# PowerDistributionBoard.net
KiCad netlist of a schematic drawn in EAGLE
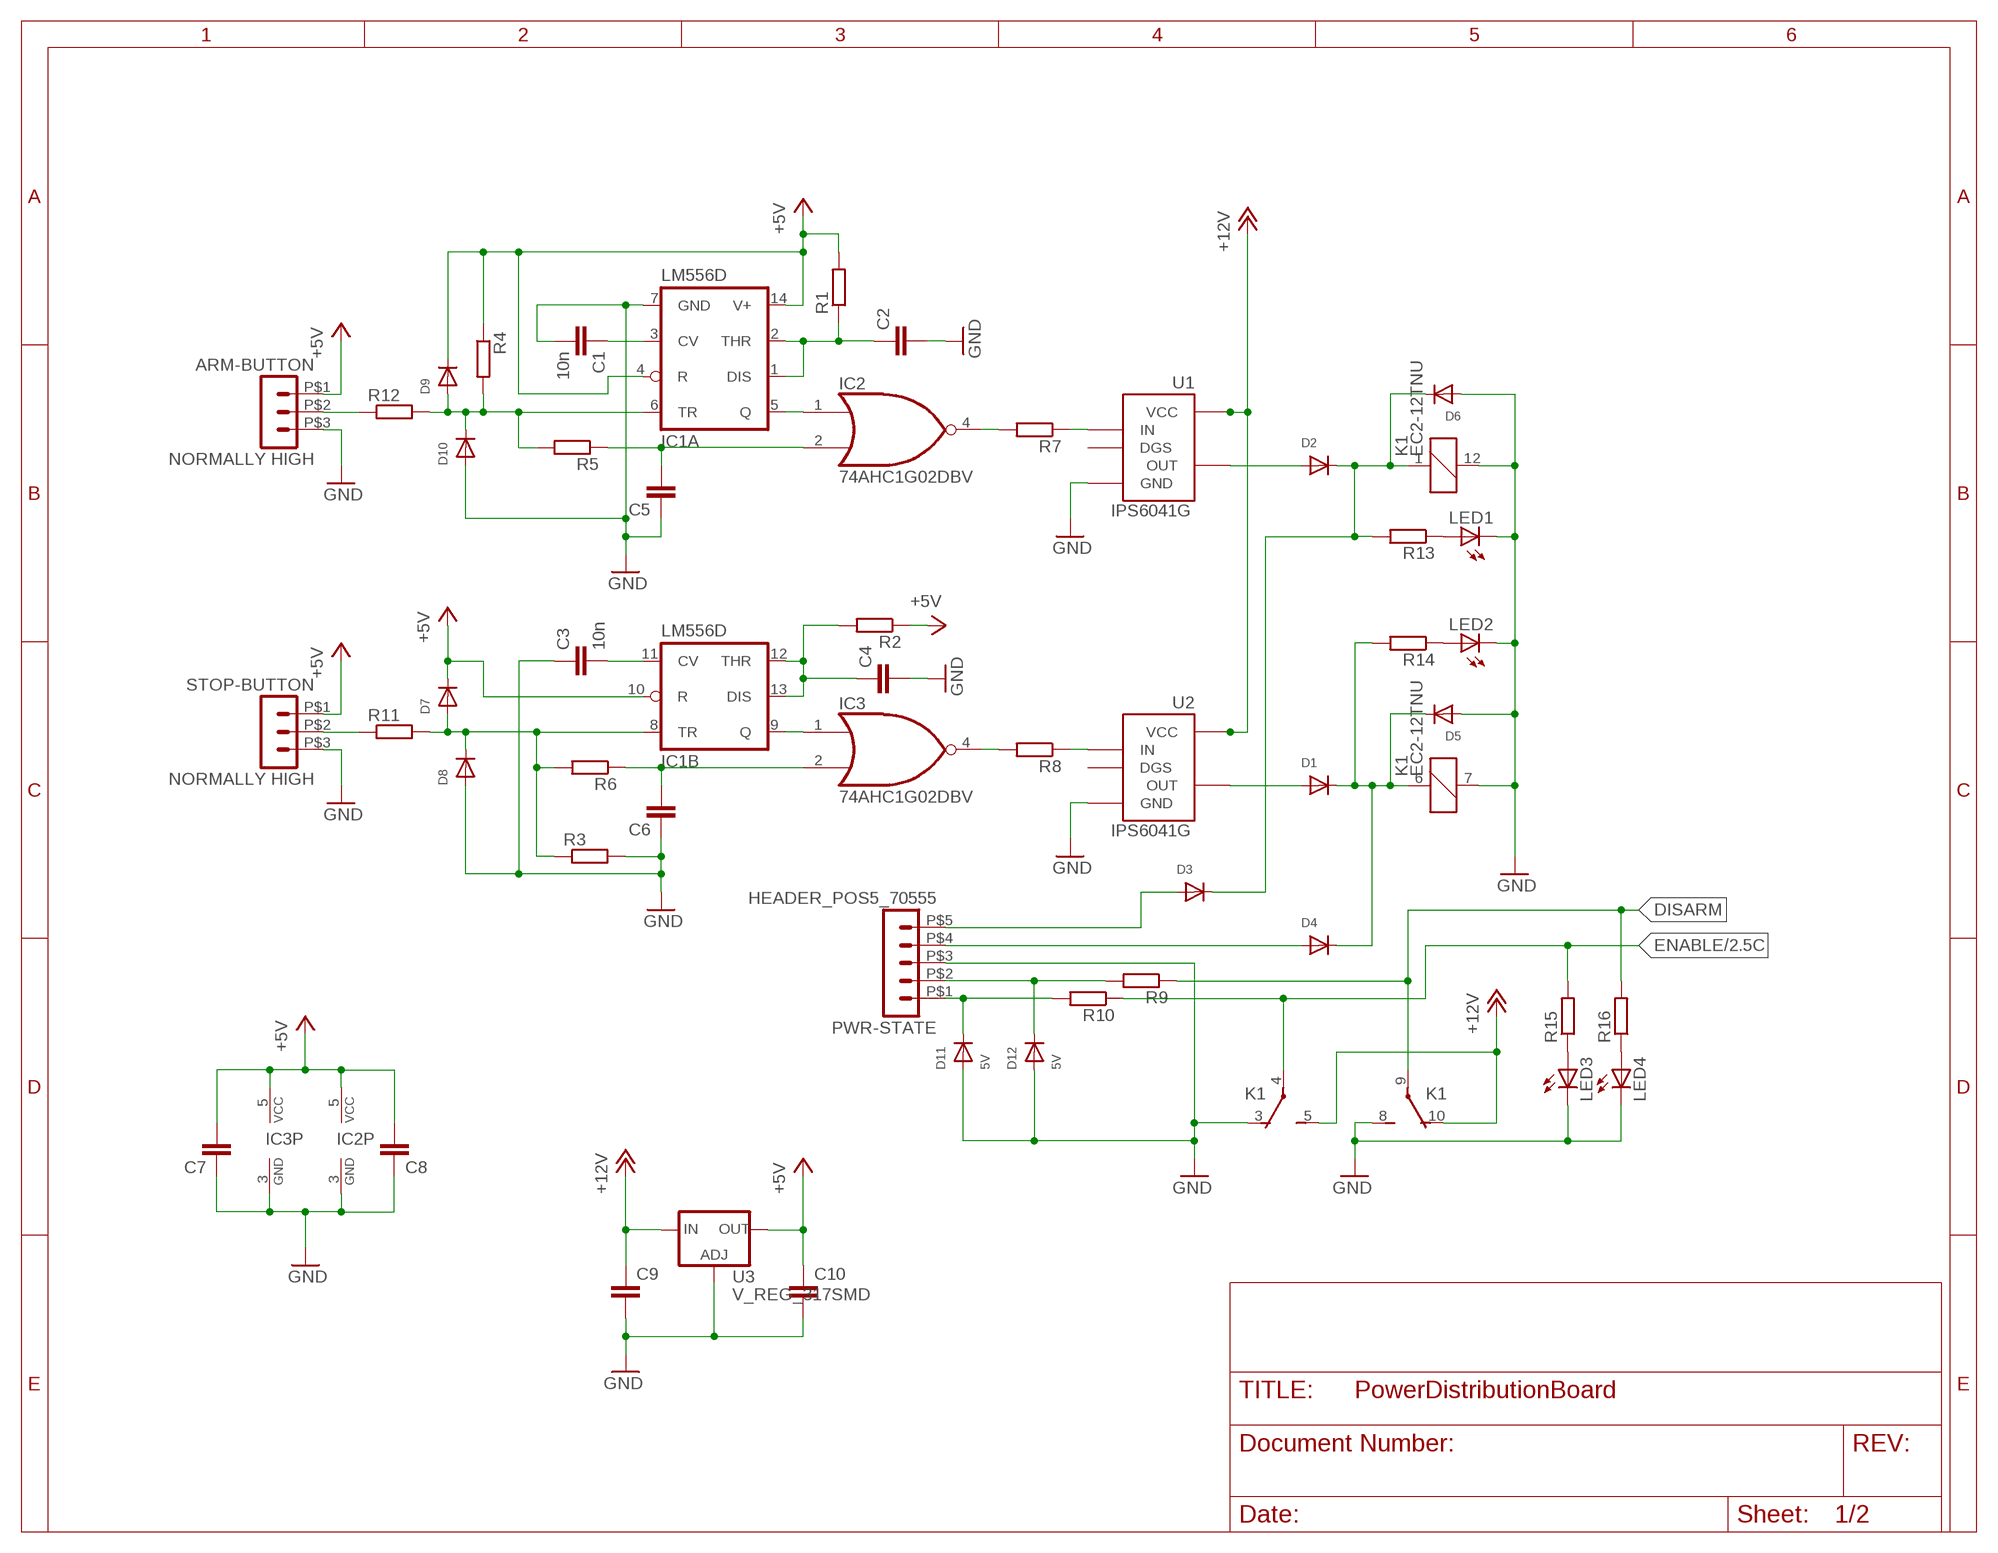
[diagram p0: schematic, sheet 1]
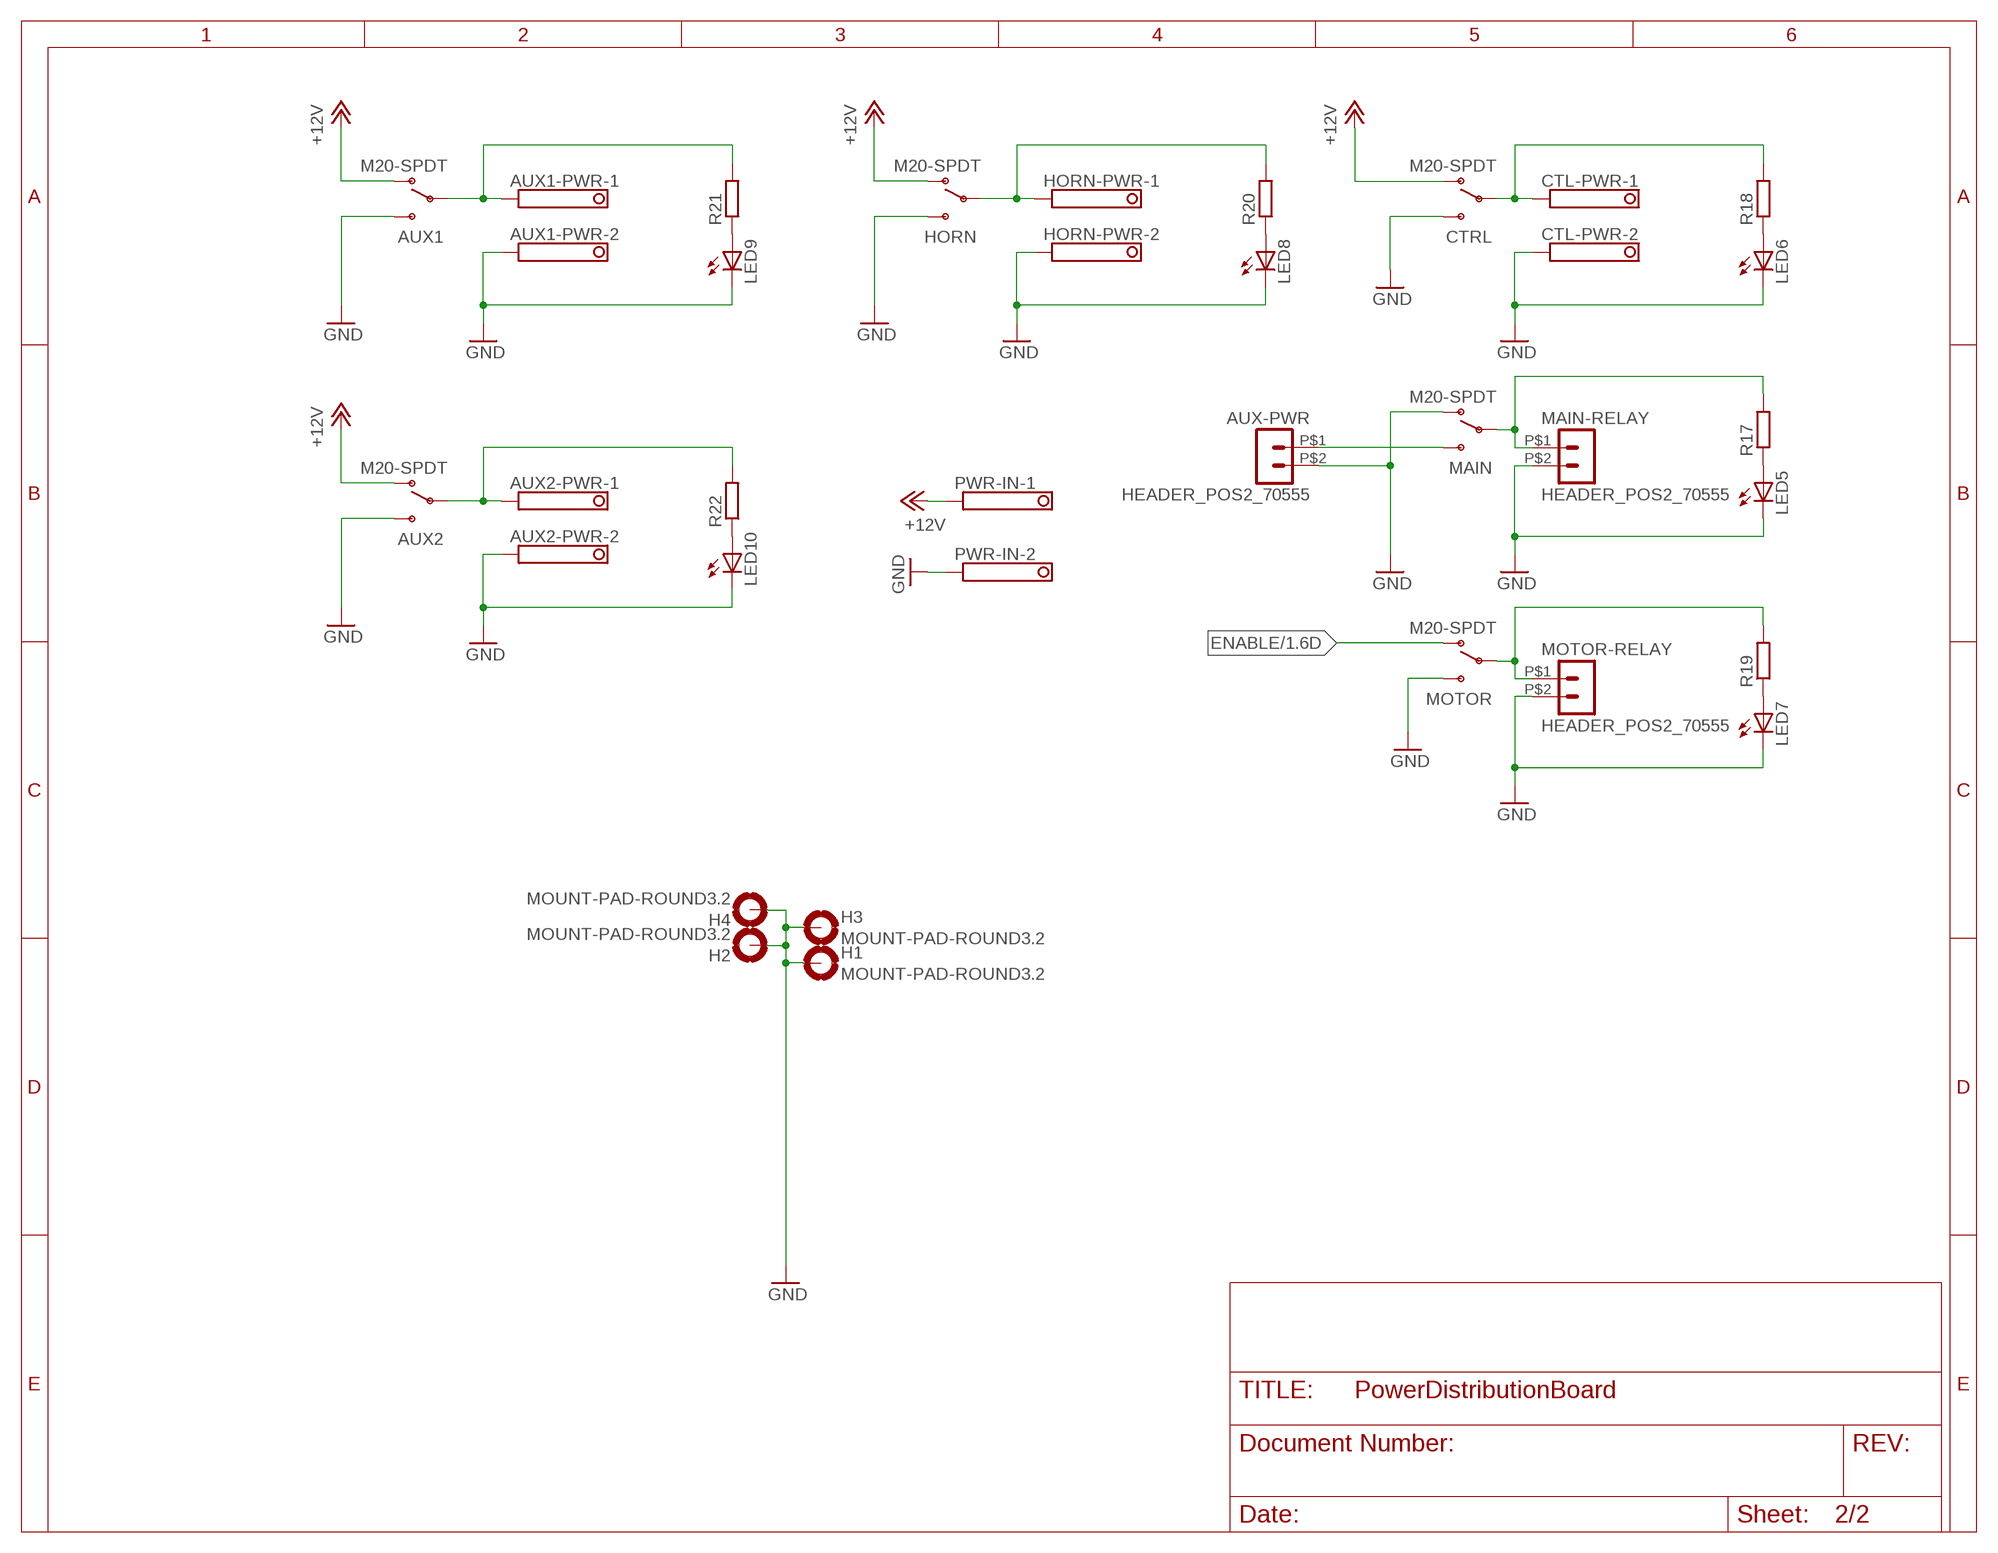
[diagram p1: schematic, sheet 2]

(export (version "E")
  (design (tool "Eeschema 10.0.6"))
  (components
    (comp (ref "ARM-BUTTON")
      (value "NORMALLY HIGH")
      (footprint "eagle-import:70555-POS3")
      (libsource (lib "eagle-import") (part "HEADER_POS3_?70555"))
    )
    (comp (ref "C1")
      (value "10n")
      (footprint "eagle-import:C0603")
      (libsource (lib "eagle-import") (part "C-EUC0603"))
    )
    (comp (ref "C2")
      (value "C-EUC0603")
      (footprint "eagle-import:C0603")
      (libsource (lib "eagle-import") (part "C-EUC0603"))
    )
    (comp (ref "C3")
      (value "10n")
      (footprint "eagle-import:C0603")
      (libsource (lib "eagle-import") (part "C-EUC0603"))
    )
    (comp (ref "C4")
      (value "C-EUC0603")
      (footprint "eagle-import:C0603")
      (libsource (lib "eagle-import") (part "C-EUC0603"))
    )
    (comp (ref "C5")
      (value "C-EUC0603")
      (footprint "eagle-import:C0603")
      (libsource (lib "eagle-import") (part "C-EUC0603"))
    )
    (comp (ref "C6")
      (value "C-EUC0603")
      (footprint "eagle-import:C0603")
      (libsource (lib "eagle-import") (part "C-EUC0603"))
    )
    (comp (ref "C7")
      (value "C-EUC0603")
      (footprint "eagle-import:C0603")
      (libsource (lib "eagle-import") (part "C-EUC0603"))
    )
    (comp (ref "C8")
      (value "C-EUC0603")
      (footprint "eagle-import:C0603")
      (libsource (lib "eagle-import") (part "C-EUC0603"))
    )
    (comp (ref "C9")
      (value "C-EUC1206")
      (footprint "eagle-import:C1206")
      (libsource (lib "eagle-import") (part "C-EUC1206"))
    )
    (comp (ref "C10")
      (value "C-EUC1206")
      (footprint "eagle-import:C1206")
      (libsource (lib "eagle-import") (part "C-EUC1206"))
    )
    (comp (ref "D1")
      (value "DIODESOD-123")
      (footprint "eagle-import:SOD-123")
      (libsource (lib "eagle-import") (part "DIODESOD-123"))
    )
    (comp (ref "D2")
      (value "DIODESOD-123")
      (footprint "eagle-import:SOD-123")
      (libsource (lib "eagle-import") (part "DIODESOD-123"))
    )
    (comp (ref "D3")
      (value "DIODESOD-123")
      (footprint "eagle-import:SOD-123")
      (libsource (lib "eagle-import") (part "DIODESOD-123"))
    )
    (comp (ref "D4")
      (value "DIODESOD-123")
      (footprint "eagle-import:SOD-123")
      (libsource (lib "eagle-import") (part "DIODESOD-123"))
    )
    (comp (ref "D5")
      (value "DIODESOD-123")
      (footprint "eagle-import:SOD-123")
      (libsource (lib "eagle-import") (part "DIODESOD-123"))
    )
    (comp (ref "D6")
      (value "DIODESOD-123")
      (footprint "eagle-import:SOD-123")
      (libsource (lib "eagle-import") (part "DIODESOD-123"))
    )
    (comp (ref "D7")
      (value "DIODESOD-123")
      (footprint "eagle-import:SOD-123")
      (libsource (lib "eagle-import") (part "DIODESOD-123"))
    )
    (comp (ref "D8")
      (value "DIODESOD-123")
      (footprint "eagle-import:SOD-123")
      (libsource (lib "eagle-import") (part "DIODESOD-123"))
    )
    (comp (ref "D9")
      (value "DIODESOD-123")
      (footprint "eagle-import:SOD-123")
      (libsource (lib "eagle-import") (part "DIODESOD-123"))
    )
    (comp (ref "D10")
      (value "DIODESOD-123")
      (footprint "eagle-import:SOD-123")
      (libsource (lib "eagle-import") (part "DIODESOD-123"))
    )
    (comp (ref "D11")
      (value "5V")
      (footprint "eagle-import:SOD-123")
      (libsource (lib "eagle-import") (part "DIODESOD-123"))
    )
    (comp (ref "D12")
      (value "5V")
      (footprint "eagle-import:SOD-123")
      (libsource (lib "eagle-import") (part "DIODESOD-123"))
    )
    (comp (ref "IC1")
      (value "LM556D")
      (footprint "eagle-import:SO14")
      (libsource (lib "eagle-import") (part "556DLM"))
    )
    (comp (ref "IC2")
      (value "74AHC1G02DBV")
      (footprint "eagle-import:SOT23-5")
      (libsource (lib "eagle-import") (part "741G02DBVAHC"))
    )
    (comp (ref "IC3")
      (value "74AHC1G02DBV")
      (footprint "eagle-import:SOT23-5")
      (libsource (lib "eagle-import") (part "741G02DBVAHC"))
    )
    (comp (ref "K1")
      (value "EC2-12TNU")
      (footprint "eagle-import:EC2-_TNU")
      (fields (field (name "PARTNO") "EC2-12TNU"))
      (libsource (lib "eagle-import") (part "EC2-12TNU"))
    )
    (comp (ref "LED1")
      (value "LEDCHIP-LED0805")
      (footprint "eagle-import:CHIP-LED0805")
      (libsource (lib "eagle-import") (part "LEDCHIP-LED0805"))
    )
    (comp (ref "LED2")
      (value "LEDCHIP-LED0805")
      (footprint "eagle-import:CHIP-LED0805")
      (libsource (lib "eagle-import") (part "LEDCHIP-LED0805"))
    )
    (comp (ref "LED3")
      (value "LEDCHIP-LED0805")
      (footprint "eagle-import:CHIP-LED0805")
      (libsource (lib "eagle-import") (part "LEDCHIP-LED0805"))
    )
    (comp (ref "LED4")
      (value "LEDCHIP-LED0805")
      (footprint "eagle-import:CHIP-LED0805")
      (libsource (lib "eagle-import") (part "LEDCHIP-LED0805"))
    )
    (comp (ref "PWR-STATE")
      (value "HEADER_POS5_70555")
      (footprint "eagle-import:70555-POS5")
      (libsource (lib "eagle-import") (part "HEADER_POS5_?70555"))
    )
    (comp (ref "R1")
      (value "R-EU_R0603")
      (footprint "eagle-import:R0603")
      (libsource (lib "eagle-import") (part "R-EU_R0603"))
    )
    (comp (ref "R2")
      (value "R-EU_R0603")
      (footprint "eagle-import:R0603")
      (libsource (lib "eagle-import") (part "R-EU_R0603"))
    )
    (comp (ref "R3")
      (value "R-EU_R0603")
      (footprint "eagle-import:R0603")
      (libsource (lib "eagle-import") (part "R-EU_R0603"))
    )
    (comp (ref "R4")
      (value "R-EU_R0603")
      (footprint "eagle-import:R0603")
      (libsource (lib "eagle-import") (part "R-EU_R0603"))
    )
    (comp (ref "R5")
      (value "R-EU_R0603")
      (footprint "eagle-import:R0603")
      (libsource (lib "eagle-import") (part "R-EU_R0603"))
    )
    (comp (ref "R6")
      (value "R-EU_R0603")
      (footprint "eagle-import:R0603")
      (libsource (lib "eagle-import") (part "R-EU_R0603"))
    )
    (comp (ref "R7")
      (value "R-EU_R0603")
      (footprint "eagle-import:R0603")
      (libsource (lib "eagle-import") (part "R-EU_R0603"))
    )
    (comp (ref "R8")
      (value "R-EU_R0603")
      (footprint "eagle-import:R0603")
      (libsource (lib "eagle-import") (part "R-EU_R0603"))
    )
    (comp (ref "R9")
      (value "R-EU_R0603")
      (footprint "eagle-import:R0603")
      (libsource (lib "eagle-import") (part "R-EU_R0603"))
    )
    (comp (ref "R10")
      (value "R-EU_R0603")
      (footprint "eagle-import:R0603")
      (libsource (lib "eagle-import") (part "R-EU_R0603"))
    )
    (comp (ref "R11")
      (value "R-EU_R0603")
      (footprint "eagle-import:R0603")
      (libsource (lib "eagle-import") (part "R-EU_R0603"))
    )
    (comp (ref "R12")
      (value "R-EU_R0603")
      (footprint "eagle-import:R0603")
      (libsource (lib "eagle-import") (part "R-EU_R0603"))
    )
    (comp (ref "R13")
      (value "R-EU_R0603")
      (footprint "eagle-import:R0603")
      (libsource (lib "eagle-import") (part "R-EU_R0603"))
    )
    (comp (ref "R14")
      (value "R-EU_R0603")
      (footprint "eagle-import:R0603")
      (libsource (lib "eagle-import") (part "R-EU_R0603"))
    )
    (comp (ref "R15")
      (value "R-EU_R0603")
      (footprint "eagle-import:R0603")
      (libsource (lib "eagle-import") (part "R-EU_R0603"))
    )
    (comp (ref "R16")
      (value "R-EU_R0603")
      (footprint "eagle-import:R0603")
      (libsource (lib "eagle-import") (part "R-EU_R0603"))
    )
    (comp (ref "STOP-BUTTON")
      (value "NORMALLY HIGH")
      (footprint "eagle-import:70555-POS3")
      (libsource (lib "eagle-import") (part "HEADER_POS3_?70555"))
    )
    (comp (ref "U1")
      (value "IPS6041G")
      (footprint "eagle-import:SO08")
      (libsource (lib "eagle-import") (part "IPS6041G"))
    )
    (comp (ref "U2")
      (value "IPS6041G")
      (footprint "eagle-import:SO08")
      (libsource (lib "eagle-import") (part "IPS6041G"))
    )
    (comp (ref "U3")
      (value "V_REG_317SMD")
      (footprint "eagle-import:SOT223")
      (libsource (lib "eagle-import") (part "V_REG_317SMD"))
    )
    (comp (ref "AUX-PWR")
      (value "HEADER_POS2_70555")
      (footprint "eagle-import:70555-POS2")
      (libsource (lib "eagle-import") (part "HEADER_POS2_?70555"))
    )
    (comp (ref "AUX1")
      (value "M20-SPDT")
      (footprint "eagle-import:M20-SPDT")
      (libsource (lib "eagle-import") (part "M20-SPDT"))
    )
    (comp (ref "AUX1-PWR")
      (value "1751248")
      (footprint "eagle-import:1751248")
      (libsource (lib "eagle-import") (part "1751248"))
    )
    (comp (ref "AUX2")
      (value "M20-SPDT")
      (footprint "eagle-import:M20-SPDT")
      (libsource (lib "eagle-import") (part "M20-SPDT"))
    )
    (comp (ref "AUX2-PWR")
      (value "1751248")
      (footprint "eagle-import:1751248")
      (libsource (lib "eagle-import") (part "1751248"))
    )
    (comp (ref "CTL-PWR")
      (value "1751248")
      (footprint "eagle-import:1751248")
      (libsource (lib "eagle-import") (part "1751248"))
    )
    (comp (ref "CTRL")
      (value "M20-SPDT")
      (footprint "eagle-import:M20-SPDT")
      (libsource (lib "eagle-import") (part "M20-SPDT"))
    )
    (comp (ref "H1")
      (value "MOUNT-PAD-ROUND3.2")
      (footprint "eagle-import:3,2-PAD")
      (libsource (lib "eagle-import") (part "MOUNT-PAD-ROUND3.2"))
    )
    (comp (ref "H2")
      (value "MOUNT-PAD-ROUND3.2")
      (footprint "eagle-import:3,2-PAD")
      (libsource (lib "eagle-import") (part "MOUNT-PAD-ROUND3.2"))
    )
    (comp (ref "H3")
      (value "MOUNT-PAD-ROUND3.2")
      (footprint "eagle-import:3,2-PAD")
      (libsource (lib "eagle-import") (part "MOUNT-PAD-ROUND3.2"))
    )
    (comp (ref "H4")
      (value "MOUNT-PAD-ROUND3.2")
      (footprint "eagle-import:3,2-PAD")
      (libsource (lib "eagle-import") (part "MOUNT-PAD-ROUND3.2"))
    )
    (comp (ref "HORN")
      (value "M20-SPDT")
      (footprint "eagle-import:M20-SPDT")
      (libsource (lib "eagle-import") (part "M20-SPDT"))
    )
    (comp (ref "HORN-PWR")
      (value "1751248")
      (footprint "eagle-import:1751248")
      (libsource (lib "eagle-import") (part "1751248"))
    )
    (comp (ref "LED5")
      (value "LEDCHIP-LED0805")
      (footprint "eagle-import:CHIP-LED0805")
      (libsource (lib "eagle-import") (part "LEDCHIP-LED0805"))
    )
    (comp (ref "LED6")
      (value "LEDCHIP-LED0805")
      (footprint "eagle-import:CHIP-LED0805")
      (libsource (lib "eagle-import") (part "LEDCHIP-LED0805"))
    )
    (comp (ref "LED7")
      (value "LEDCHIP-LED0805")
      (footprint "eagle-import:CHIP-LED0805")
      (libsource (lib "eagle-import") (part "LEDCHIP-LED0805"))
    )
    (comp (ref "LED8")
      (value "LEDCHIP-LED0805")
      (footprint "eagle-import:CHIP-LED0805")
      (libsource (lib "eagle-import") (part "LEDCHIP-LED0805"))
    )
    (comp (ref "LED9")
      (value "LEDCHIP-LED0805")
      (footprint "eagle-import:CHIP-LED0805")
      (libsource (lib "eagle-import") (part "LEDCHIP-LED0805"))
    )
    (comp (ref "LED10")
      (value "LEDCHIP-LED0805")
      (footprint "eagle-import:CHIP-LED0805")
      (libsource (lib "eagle-import") (part "LEDCHIP-LED0805"))
    )
    (comp (ref "MAIN")
      (value "M20-SPDT")
      (footprint "eagle-import:M20-SPDT")
      (libsource (lib "eagle-import") (part "M20-SPDT"))
    )
    (comp (ref "MAIN-RELAY")
      (value "HEADER_POS2_70555")
      (footprint "eagle-import:70555-POS2")
      (libsource (lib "eagle-import") (part "HEADER_POS2_?70555"))
    )
    (comp (ref "MOTOR")
      (value "M20-SPDT")
      (footprint "eagle-import:M20-SPDT")
      (libsource (lib "eagle-import") (part "M20-SPDT"))
    )
    (comp (ref "MOTOR-RELAY")
      (value "HEADER_POS2_70555")
      (footprint "eagle-import:70555-POS2")
      (libsource (lib "eagle-import") (part "HEADER_POS2_?70555"))
    )
    (comp (ref "PWR-IN")
      (value "1751248")
      (footprint "eagle-import:1751248")
      (libsource (lib "eagle-import") (part "1751248"))
    )
    (comp (ref "R17")
      (value "R-EU_R0603")
      (footprint "eagle-import:R0603")
      (libsource (lib "eagle-import") (part "R-EU_R0603"))
    )
    (comp (ref "R18")
      (value "R-EU_R0603")
      (footprint "eagle-import:R0603")
      (libsource (lib "eagle-import") (part "R-EU_R0603"))
    )
    (comp (ref "R19")
      (value "R-EU_R0603")
      (footprint "eagle-import:R0603")
      (libsource (lib "eagle-import") (part "R-EU_R0603"))
    )
    (comp (ref "R20")
      (value "R-EU_R0603")
      (footprint "eagle-import:R0603")
      (libsource (lib "eagle-import") (part "R-EU_R0603"))
    )
    (comp (ref "R21")
      (value "R-EU_R0603")
      (footprint "eagle-import:R0603")
      (libsource (lib "eagle-import") (part "R-EU_R0603"))
    )
    (comp (ref "R22")
      (value "R-EU_R0603")
      (footprint "eagle-import:R0603")
      (libsource (lib "eagle-import") (part "R-EU_R0603"))
    )
  )
  (nets
    (net (code "1") (name "+5V") (class "Default")
      (node (ref "ARM-BUTTON") (pin "P$1") (pinfunction "1_P$1") (pintype "passive"))
      (node (ref "C10") (pin "1") (pinfunction "1_1") (pintype "passive"))
      (node (ref "C7") (pin "2") (pinfunction "2_2") (pintype "passive"))
      (node (ref "C8") (pin "2") (pinfunction "2_2") (pintype "passive"))
      (node (ref "D7") (pin "C") (pinfunction "C_C") (pintype "passive"))
      (node (ref "D9") (pin "C") (pinfunction "C_C") (pintype "passive"))
      (node (ref "IC1") (pin "10") (pinfunction "R_10") (pintype "input"))
      (node (ref "IC1") (pin "14") (pinfunction "V+_14") (pintype "power_in"))
      (node (ref "IC1") (pin "4") (pinfunction "R_4") (pintype "input"))
      (node (ref "IC2") (pin "5") (pinfunction "VCC_5") (pintype "power_in"))
      (node (ref "IC3") (pin "5") (pinfunction "VCC_5") (pintype "power_in"))
      (node (ref "R1") (pin "2") (pinfunction "2_2") (pintype "passive"))
      (node (ref "R2") (pin "1") (pinfunction "1_1") (pintype "passive"))
      (node (ref "R4") (pin "1") (pinfunction "1_1") (pintype "passive"))
      (node (ref "STOP-BUTTON") (pin "P$1") (pinfunction "1_P$1") (pintype "passive"))
      (node (ref "U3") (pin "2") (pinfunction "OUT_2") (pintype "output"))
    )
    (net (code "2") (name "+12V") (class "Default")
      (node (ref "AUX1") (pin "1") (pinfunction "O_1") (pintype "passive"))
      (node (ref "AUX2") (pin "1") (pinfunction "O_1") (pintype "passive"))
      (node (ref "C9") (pin "1") (pinfunction "1_1") (pintype "passive"))
      (node (ref "CTRL") (pin "1") (pinfunction "O_1") (pintype "passive"))
      (node (ref "HORN") (pin "1") (pinfunction "O_1") (pintype "passive"))
      (node (ref "K1") (pin "10") (pinfunction "O_10") (pintype "passive"))
      (node (ref "K1") (pin "5") (pinfunction "S_5") (pintype "passive"))
      (node (ref "PWR-IN") (pin "1") (pinfunction "K_1") (pintype "passive"))
      (node (ref "U1") (pin "5") (pinfunction "VCC_5") (pintype "passive"))
      (node (ref "U1") (pin "6") (pinfunction "VCC_6") (pintype "passive"))
      (node (ref "U1") (pin "7") (pinfunction "VCC_7") (pintype "passive"))
      (node (ref "U1") (pin "8") (pinfunction "VCC_8") (pintype "passive"))
      (node (ref "U2") (pin "5") (pinfunction "VCC_5") (pintype "passive"))
      (node (ref "U2") (pin "6") (pinfunction "VCC_6") (pintype "passive"))
      (node (ref "U2") (pin "7") (pinfunction "VCC_7") (pintype "passive"))
      (node (ref "U2") (pin "8") (pinfunction "VCC_8") (pintype "passive"))
      (node (ref "U3") (pin "3") (pinfunction "IN_3") (pintype "input"))
    )
    (net (code "3") (name "DISARM") (class "Default")
      (node (ref "K1") (pin "9") (pinfunction "P_9") (pintype "passive"))
      (node (ref "R16") (pin "2") (pinfunction "2_2") (pintype "passive"))
      (node (ref "R9") (pin "1") (pinfunction "1_1") (pintype "passive"))
    )
    (net (code "4") (name "ENABLE") (class "Default")
      (node (ref "K1") (pin "4") (pinfunction "P_4") (pintype "passive"))
      (node (ref "MOTOR") (pin "1") (pinfunction "O_1") (pintype "passive"))
      (node (ref "R10") (pin "1") (pinfunction "1_1") (pintype "passive"))
      (node (ref "R15") (pin "2") (pinfunction "2_2") (pintype "passive"))
    )
    (net (code "5") (name "GND") (class "Default")
      (node (ref "ARM-BUTTON") (pin "P$3") (pinfunction "3_P$3") (pintype "passive"))
      (node (ref "AUX-PWR") (pin "P$2") (pinfunction "2_P$2") (pintype "passive"))
      (node (ref "AUX1") (pin "3") (pinfunction "S_3") (pintype "passive"))
      (node (ref "AUX1-PWR") (pin "2") (pinfunction "K_2") (pintype "passive"))
      (node (ref "AUX2") (pin "3") (pinfunction "S_3") (pintype "passive"))
      (node (ref "AUX2-PWR") (pin "2") (pinfunction "K_2") (pintype "passive"))
      (node (ref "C1") (pin "2") (pinfunction "2_2") (pintype "passive"))
      (node (ref "C10") (pin "2") (pinfunction "2_2") (pintype "passive"))
      (node (ref "C2") (pin "2") (pinfunction "2_2") (pintype "passive"))
      (node (ref "C3") (pin "1") (pinfunction "1_1") (pintype "passive"))
      (node (ref "C4") (pin "2") (pinfunction "2_2") (pintype "passive"))
      (node (ref "C5") (pin "1") (pinfunction "1_1") (pintype "passive"))
      (node (ref "C6") (pin "1") (pinfunction "1_1") (pintype "passive"))
      (node (ref "C7") (pin "1") (pinfunction "1_1") (pintype "passive"))
      (node (ref "C8") (pin "1") (pinfunction "1_1") (pintype "passive"))
      (node (ref "C9") (pin "2") (pinfunction "2_2") (pintype "passive"))
      (node (ref "CTL-PWR") (pin "2") (pinfunction "K_2") (pintype "passive"))
      (node (ref "CTRL") (pin "3") (pinfunction "S_3") (pintype "passive"))
      (node (ref "D10") (pin "A") (pinfunction "A_A") (pintype "passive"))
      (node (ref "D11") (pin "A") (pinfunction "A_A") (pintype "passive"))
      (node (ref "D12") (pin "A") (pinfunction "A_A") (pintype "passive"))
      (node (ref "D5") (pin "A") (pinfunction "A_A") (pintype "passive"))
      (node (ref "D6") (pin "A") (pinfunction "A_A") (pintype "passive"))
      (node (ref "D8") (pin "A") (pinfunction "A_A") (pintype "passive"))
      (node (ref "H1") (pin "B3,2") (pinfunction "MOUNT_B3,2") (pintype "passive"))
      (node (ref "H2") (pin "B3,2") (pinfunction "MOUNT_B3,2") (pintype "passive"))
      (node (ref "H3") (pin "B3,2") (pinfunction "MOUNT_B3,2") (pintype "passive"))
      (node (ref "H4") (pin "B3,2") (pinfunction "MOUNT_B3,2") (pintype "passive"))
      (node (ref "HORN") (pin "3") (pinfunction "S_3") (pintype "passive"))
      (node (ref "HORN-PWR") (pin "2") (pinfunction "K_2") (pintype "passive"))
      (node (ref "IC1") (pin "7") (pinfunction "GND_7") (pintype "power_in"))
      (node (ref "IC2") (pin "3") (pinfunction "GND_3") (pintype "power_in"))
      (node (ref "IC3") (pin "3") (pinfunction "GND_3") (pintype "power_in"))
      (node (ref "K1") (pin "12") (pinfunction "2_12") (pintype "passive"))
      (node (ref "K1") (pin "3") (pinfunction "O_3") (pintype "passive"))
      (node (ref "K1") (pin "7") (pinfunction "2_7") (pintype "passive"))
      (node (ref "K1") (pin "8") (pinfunction "S_8") (pintype "passive"))
      (node (ref "LED1") (pin "C") (pinfunction "C_C") (pintype "passive"))
      (node (ref "LED10") (pin "C") (pinfunction "C_C") (pintype "passive"))
      (node (ref "LED2") (pin "C") (pinfunction "C_C") (pintype "passive"))
      (node (ref "LED3") (pin "C") (pinfunction "C_C") (pintype "passive"))
      (node (ref "LED4") (pin "C") (pinfunction "C_C") (pintype "passive"))
      (node (ref "LED5") (pin "C") (pinfunction "C_C") (pintype "passive"))
      (node (ref "LED6") (pin "C") (pinfunction "C_C") (pintype "passive"))
      (node (ref "LED7") (pin "C") (pinfunction "C_C") (pintype "passive"))
      (node (ref "LED8") (pin "C") (pinfunction "C_C") (pintype "passive"))
      (node (ref "LED9") (pin "C") (pinfunction "C_C") (pintype "passive"))
      (node (ref "MAIN") (pin "1") (pinfunction "O_1") (pintype "passive"))
      (node (ref "MAIN-RELAY") (pin "P$2") (pinfunction "2_P$2") (pintype "passive"))
      (node (ref "MOTOR") (pin "3") (pinfunction "S_3") (pintype "passive"))
      (node (ref "MOTOR-RELAY") (pin "P$2") (pinfunction "2_P$2") (pintype "passive"))
      (node (ref "PWR-IN") (pin "2") (pinfunction "K_2") (pintype "passive"))
      (node (ref "PWR-STATE") (pin "P$3") (pinfunction "3_P$3") (pintype "passive"))
      (node (ref "R3") (pin "2") (pinfunction "2_2") (pintype "passive"))
      (node (ref "STOP-BUTTON") (pin "P$3") (pinfunction "3_P$3") (pintype "passive"))
      (node (ref "U1") (pin "1") (pinfunction "GND_1") (pintype "passive"))
      (node (ref "U2") (pin "1") (pinfunction "GND_1") (pintype "passive"))
      (node (ref "U3") (pin "1") (pinfunction "ADJ_1") (pintype "input"))
    )
    (net (code "6") (name "Net-(ARM-BUTTON-2)") (class "Default")
      (node (ref "ARM-BUTTON") (pin "P$2") (pinfunction "2_P$2") (pintype "passive"))
      (node (ref "R12") (pin "1") (pinfunction "1_1") (pintype "passive"))
    )
    (net (code "7") (name "Net-(AUX-PWR-1)") (class "Default")
      (node (ref "AUX-PWR") (pin "P$1") (pinfunction "1_P$1") (pintype "passive"))
      (node (ref "MAIN") (pin "3") (pinfunction "S_3") (pintype "passive"))
    )
    (net (code "8") (name "Net-(AUX1-P)") (class "Default")
      (node (ref "AUX1") (pin "2") (pinfunction "P_2") (pintype "passive"))
      (node (ref "AUX1-PWR") (pin "1") (pinfunction "K_1") (pintype "passive"))
      (node (ref "R21") (pin "2") (pinfunction "2_2") (pintype "passive"))
    )
    (net (code "9") (name "Net-(AUX2-P)") (class "Default")
      (node (ref "AUX2") (pin "2") (pinfunction "P_2") (pintype "passive"))
      (node (ref "AUX2-PWR") (pin "1") (pinfunction "K_1") (pintype "passive"))
      (node (ref "R22") (pin "2") (pinfunction "2_2") (pintype "passive"))
    )
    (net (code "10") (name "Net-(CTL-PWRA-K)") (class "Default")
      (node (ref "CTL-PWR") (pin "1") (pinfunction "K_1") (pintype "passive"))
      (node (ref "CTRL") (pin "2") (pinfunction "P_2") (pintype "passive"))
      (node (ref "R18") (pin "2") (pinfunction "2_2") (pintype "passive"))
    )
    (net (code "11") (name "Net-(D2-PadC)") (class "Default")
      (node (ref "D2") (pin "C") (pinfunction "C_C") (pintype "passive"))
      (node (ref "D3") (pin "C") (pinfunction "C_C") (pintype "passive"))
      (node (ref "D6") (pin "C") (pinfunction "C_C") (pintype "passive"))
      (node (ref "K1") (pin "1") (pinfunction "1_1") (pintype "passive"))
      (node (ref "R13") (pin "2") (pinfunction "2_2") (pintype "passive"))
    )
    (net (code "12") (name "Net-(HORN-P)") (class "Default")
      (node (ref "HORN") (pin "2") (pinfunction "P_2") (pintype "passive"))
      (node (ref "HORN-PWR") (pin "1") (pinfunction "K_1") (pintype "passive"))
      (node (ref "R20") (pin "2") (pinfunction "2_2") (pintype "passive"))
    )
    (net (code "13") (name "Net-(IC1A-CV)") (class "Default")
      (node (ref "C1") (pin "1") (pinfunction "1_1") (pintype "passive"))
      (node (ref "IC1") (pin "3") (pinfunction "CV_3") (pintype "input"))
    )
    (net (code "14") (name "Net-(IC1A-DIS)") (class "Default")
      (node (ref "C2") (pin "1") (pinfunction "1_1") (pintype "passive"))
      (node (ref "IC1") (pin "1") (pinfunction "DIS_1") (pintype "input"))
      (node (ref "IC1") (pin "2") (pinfunction "THR_2") (pintype "input"))
      (node (ref "R1") (pin "1") (pinfunction "1_1") (pintype "passive"))
    )
    (net (code "15") (name "Net-(IC1A-Q)") (class "Default")
      (node (ref "IC1") (pin "5") (pinfunction "Q_5") (pintype "output"))
      (node (ref "IC2") (pin "1") (pinfunction "I0_1") (pintype "input"))
    )
    (net (code "16") (name "Net-(IC1A-TR)") (class "Default")
      (node (ref "D10") (pin "C") (pinfunction "C_C") (pintype "passive"))
      (node (ref "D9") (pin "A") (pinfunction "A_A") (pintype "passive"))
      (node (ref "IC1") (pin "6") (pinfunction "TR_6") (pintype "input"))
      (node (ref "R12") (pin "2") (pinfunction "2_2") (pintype "passive"))
      (node (ref "R4") (pin "2") (pinfunction "2_2") (pintype "passive"))
      (node (ref "R5") (pin "2") (pinfunction "2_2") (pintype "passive"))
    )
    (net (code "17") (name "Net-(IC1B-CV)") (class "Default")
      (node (ref "C3") (pin "2") (pinfunction "2_2") (pintype "passive"))
      (node (ref "IC1") (pin "11") (pinfunction "CV_11") (pintype "input"))
    )
    (net (code "18") (name "Net-(IC1B-DIS)") (class "Default")
      (node (ref "C4") (pin "1") (pinfunction "1_1") (pintype "passive"))
      (node (ref "IC1") (pin "12") (pinfunction "THR_12") (pintype "input"))
      (node (ref "IC1") (pin "13") (pinfunction "DIS_13") (pintype "input"))
      (node (ref "R2") (pin "2") (pinfunction "2_2") (pintype "passive"))
    )
    (net (code "19") (name "Net-(IC1B-Q)") (class "Default")
      (node (ref "IC1") (pin "9") (pinfunction "Q_9") (pintype "output"))
      (node (ref "IC3") (pin "1") (pinfunction "I0_1") (pintype "input"))
    )
    (net (code "20") (name "Net-(IC1B-TR)") (class "Default")
      (node (ref "D7") (pin "A") (pinfunction "A_A") (pintype "passive"))
      (node (ref "D8") (pin "C") (pinfunction "C_C") (pintype "passive"))
      (node (ref "IC1") (pin "8") (pinfunction "TR_8") (pintype "input"))
      (node (ref "R11") (pin "2") (pinfunction "2_2") (pintype "passive"))
      (node (ref "R3") (pin "1") (pinfunction "1_1") (pintype "passive"))
      (node (ref "R6") (pin "2") (pinfunction "2_2") (pintype "passive"))
    )
    (net (code "21") (name "Net-(IC2A-I1)") (class "Default")
      (node (ref "C5") (pin "2") (pinfunction "2_2") (pintype "passive"))
      (node (ref "IC2") (pin "2") (pinfunction "I1_2") (pintype "input"))
      (node (ref "R5") (pin "1") (pinfunction "1_1") (pintype "passive"))
    )
    (net (code "22") (name "Net-(IC2A-O)") (class "Default")
      (node (ref "IC2") (pin "4") (pinfunction "O_4") (pintype "output"))
      (node (ref "R7") (pin "2") (pinfunction "2_2") (pintype "passive"))
    )
    (net (code "23") (name "Net-(IC3A-I1)") (class "Default")
      (node (ref "C6") (pin "2") (pinfunction "2_2") (pintype "passive"))
      (node (ref "IC3") (pin "2") (pinfunction "I1_2") (pintype "input"))
      (node (ref "R6") (pin "1") (pinfunction "1_1") (pintype "passive"))
    )
    (net (code "24") (name "Net-(IC3A-O)") (class "Default")
      (node (ref "IC3") (pin "4") (pinfunction "O_4") (pintype "output"))
      (node (ref "R8") (pin "2") (pinfunction "2_2") (pintype "passive"))
    )
    (net (code "25") (name "Net-(K1C-1)") (class "Default")
      (node (ref "D1") (pin "C") (pinfunction "C_C") (pintype "passive"))
      (node (ref "D4") (pin "C") (pinfunction "C_C") (pintype "passive"))
      (node (ref "D5") (pin "C") (pinfunction "C_C") (pintype "passive"))
      (node (ref "K1") (pin "6") (pinfunction "1_6") (pintype "passive"))
      (node (ref "R14") (pin "2") (pinfunction "2_2") (pintype "passive"))
    )
    (net (code "26") (name "Net-(LED1-PadA)") (class "Default")
      (node (ref "LED1") (pin "A") (pinfunction "A_A") (pintype "passive"))
      (node (ref "R13") (pin "1") (pinfunction "1_1") (pintype "passive"))
    )
    (net (code "27") (name "Net-(LED2-PadA)") (class "Default")
      (node (ref "LED2") (pin "A") (pinfunction "A_A") (pintype "passive"))
      (node (ref "R14") (pin "1") (pinfunction "1_1") (pintype "passive"))
    )
    (net (code "28") (name "Net-(LED3-PadA)") (class "Default")
      (node (ref "LED3") (pin "A") (pinfunction "A_A") (pintype "passive"))
      (node (ref "R15") (pin "1") (pinfunction "1_1") (pintype "passive"))
    )
    (net (code "29") (name "Net-(LED4-PadA)") (class "Default")
      (node (ref "LED4") (pin "A") (pinfunction "A_A") (pintype "passive"))
      (node (ref "R16") (pin "1") (pinfunction "1_1") (pintype "passive"))
    )
    (net (code "30") (name "Net-(LED5-PadA)") (class "Default")
      (node (ref "LED5") (pin "A") (pinfunction "A_A") (pintype "passive"))
      (node (ref "R17") (pin "1") (pinfunction "1_1") (pintype "passive"))
    )
    (net (code "31") (name "Net-(LED6-PadA)") (class "Default")
      (node (ref "LED6") (pin "A") (pinfunction "A_A") (pintype "passive"))
      (node (ref "R18") (pin "1") (pinfunction "1_1") (pintype "passive"))
    )
    (net (code "32") (name "Net-(LED7-PadA)") (class "Default")
      (node (ref "LED7") (pin "A") (pinfunction "A_A") (pintype "passive"))
      (node (ref "R19") (pin "1") (pinfunction "1_1") (pintype "passive"))
    )
    (net (code "33") (name "Net-(LED8-PadA)") (class "Default")
      (node (ref "LED8") (pin "A") (pinfunction "A_A") (pintype "passive"))
      (node (ref "R20") (pin "1") (pinfunction "1_1") (pintype "passive"))
    )
    (net (code "34") (name "Net-(LED9-PadA)") (class "Default")
      (node (ref "LED9") (pin "A") (pinfunction "A_A") (pintype "passive"))
      (node (ref "R21") (pin "1") (pinfunction "1_1") (pintype "passive"))
    )
    (net (code "35") (name "Net-(LED10-PadA)") (class "Default")
      (node (ref "LED10") (pin "A") (pinfunction "A_A") (pintype "passive"))
      (node (ref "R22") (pin "1") (pinfunction "1_1") (pintype "passive"))
    )
    (net (code "36") (name "Net-(MAIN-P)") (class "Default")
      (node (ref "MAIN") (pin "2") (pinfunction "P_2") (pintype "passive"))
      (node (ref "MAIN-RELAY") (pin "P$1") (pinfunction "1_P$1") (pintype "passive"))
      (node (ref "R17") (pin "2") (pinfunction "2_2") (pintype "passive"))
    )
    (net (code "37") (name "Net-(MOTOR-P)") (class "Default")
      (node (ref "MOTOR") (pin "2") (pinfunction "P_2") (pintype "passive"))
      (node (ref "MOTOR-RELAY") (pin "P$1") (pinfunction "1_P$1") (pintype "passive"))
      (node (ref "R19") (pin "2") (pinfunction "2_2") (pintype "passive"))
    )
    (net (code "38") (name "Net-(PWR-STATE-1)") (class "Default")
      (node (ref "D11") (pin "C") (pinfunction "C_C") (pintype "passive"))
      (node (ref "PWR-STATE") (pin "P$1") (pinfunction "1_P$1") (pintype "passive"))
      (node (ref "R10") (pin "2") (pinfunction "2_2") (pintype "passive"))
    )
    (net (code "39") (name "Net-(PWR-STATE-2)") (class "Default")
      (node (ref "D12") (pin "C") (pinfunction "C_C") (pintype "passive"))
      (node (ref "PWR-STATE") (pin "P$2") (pinfunction "2_P$2") (pintype "passive"))
      (node (ref "R9") (pin "2") (pinfunction "2_2") (pintype "passive"))
    )
    (net (code "40") (name "Net-(PWR-STATE-4)") (class "Default")
      (node (ref "D4") (pin "A") (pinfunction "A_A") (pintype "passive"))
      (node (ref "PWR-STATE") (pin "P$4") (pinfunction "4_P$4") (pintype "passive"))
    )
    (net (code "41") (name "Net-(PWR-STATE-5)") (class "Default")
      (node (ref "D3") (pin "A") (pinfunction "A_A") (pintype "passive"))
      (node (ref "PWR-STATE") (pin "P$5") (pinfunction "5_P$5") (pintype "passive"))
    )
    (net (code "42") (name "Net-(STOP-BUTTON-2)") (class "Default")
      (node (ref "R11") (pin "1") (pinfunction "1_1") (pintype "passive"))
      (node (ref "STOP-BUTTON") (pin "P$2") (pinfunction "2_P$2") (pintype "passive"))
    )
    (net (code "43") (name "Net-(U1-IN)") (class "Default")
      (node (ref "R7") (pin "1") (pinfunction "1_1") (pintype "passive"))
      (node (ref "U1") (pin "2") (pinfunction "IN_2") (pintype "input"))
    )
    (net (code "44") (name "Net-(U1-OUT)") (class "Default")
      (node (ref "D2") (pin "A") (pinfunction "A_A") (pintype "passive"))
      (node (ref "U1") (pin "4") (pinfunction "OUT_4") (pintype "output"))
    )
    (net (code "45") (name "Net-(U2-IN)") (class "Default")
      (node (ref "R8") (pin "1") (pinfunction "1_1") (pintype "passive"))
      (node (ref "U2") (pin "2") (pinfunction "IN_2") (pintype "input"))
    )
    (net (code "46") (name "Net-(U2-OUT)") (class "Default")
      (node (ref "D1") (pin "A") (pinfunction "A_A") (pintype "passive"))
      (node (ref "U2") (pin "4") (pinfunction "OUT_4") (pintype "output"))
    )
    (net (code "47") (name "unconnected-(U1-DGS-Pad3)") (class "Default")
      (node (ref "U1") (pin "3") (pinfunction "DGS_3") (pintype "output"))
    )
    (net (code "48") (name "unconnected-(U2-DGS-Pad3)") (class "Default")
      (node (ref "U2") (pin "3") (pinfunction "DGS_3") (pintype "output"))
    )
  )
)
